# aqc-dac-io-board.net
KiCad netlist of a schematic drawn in EAGLE
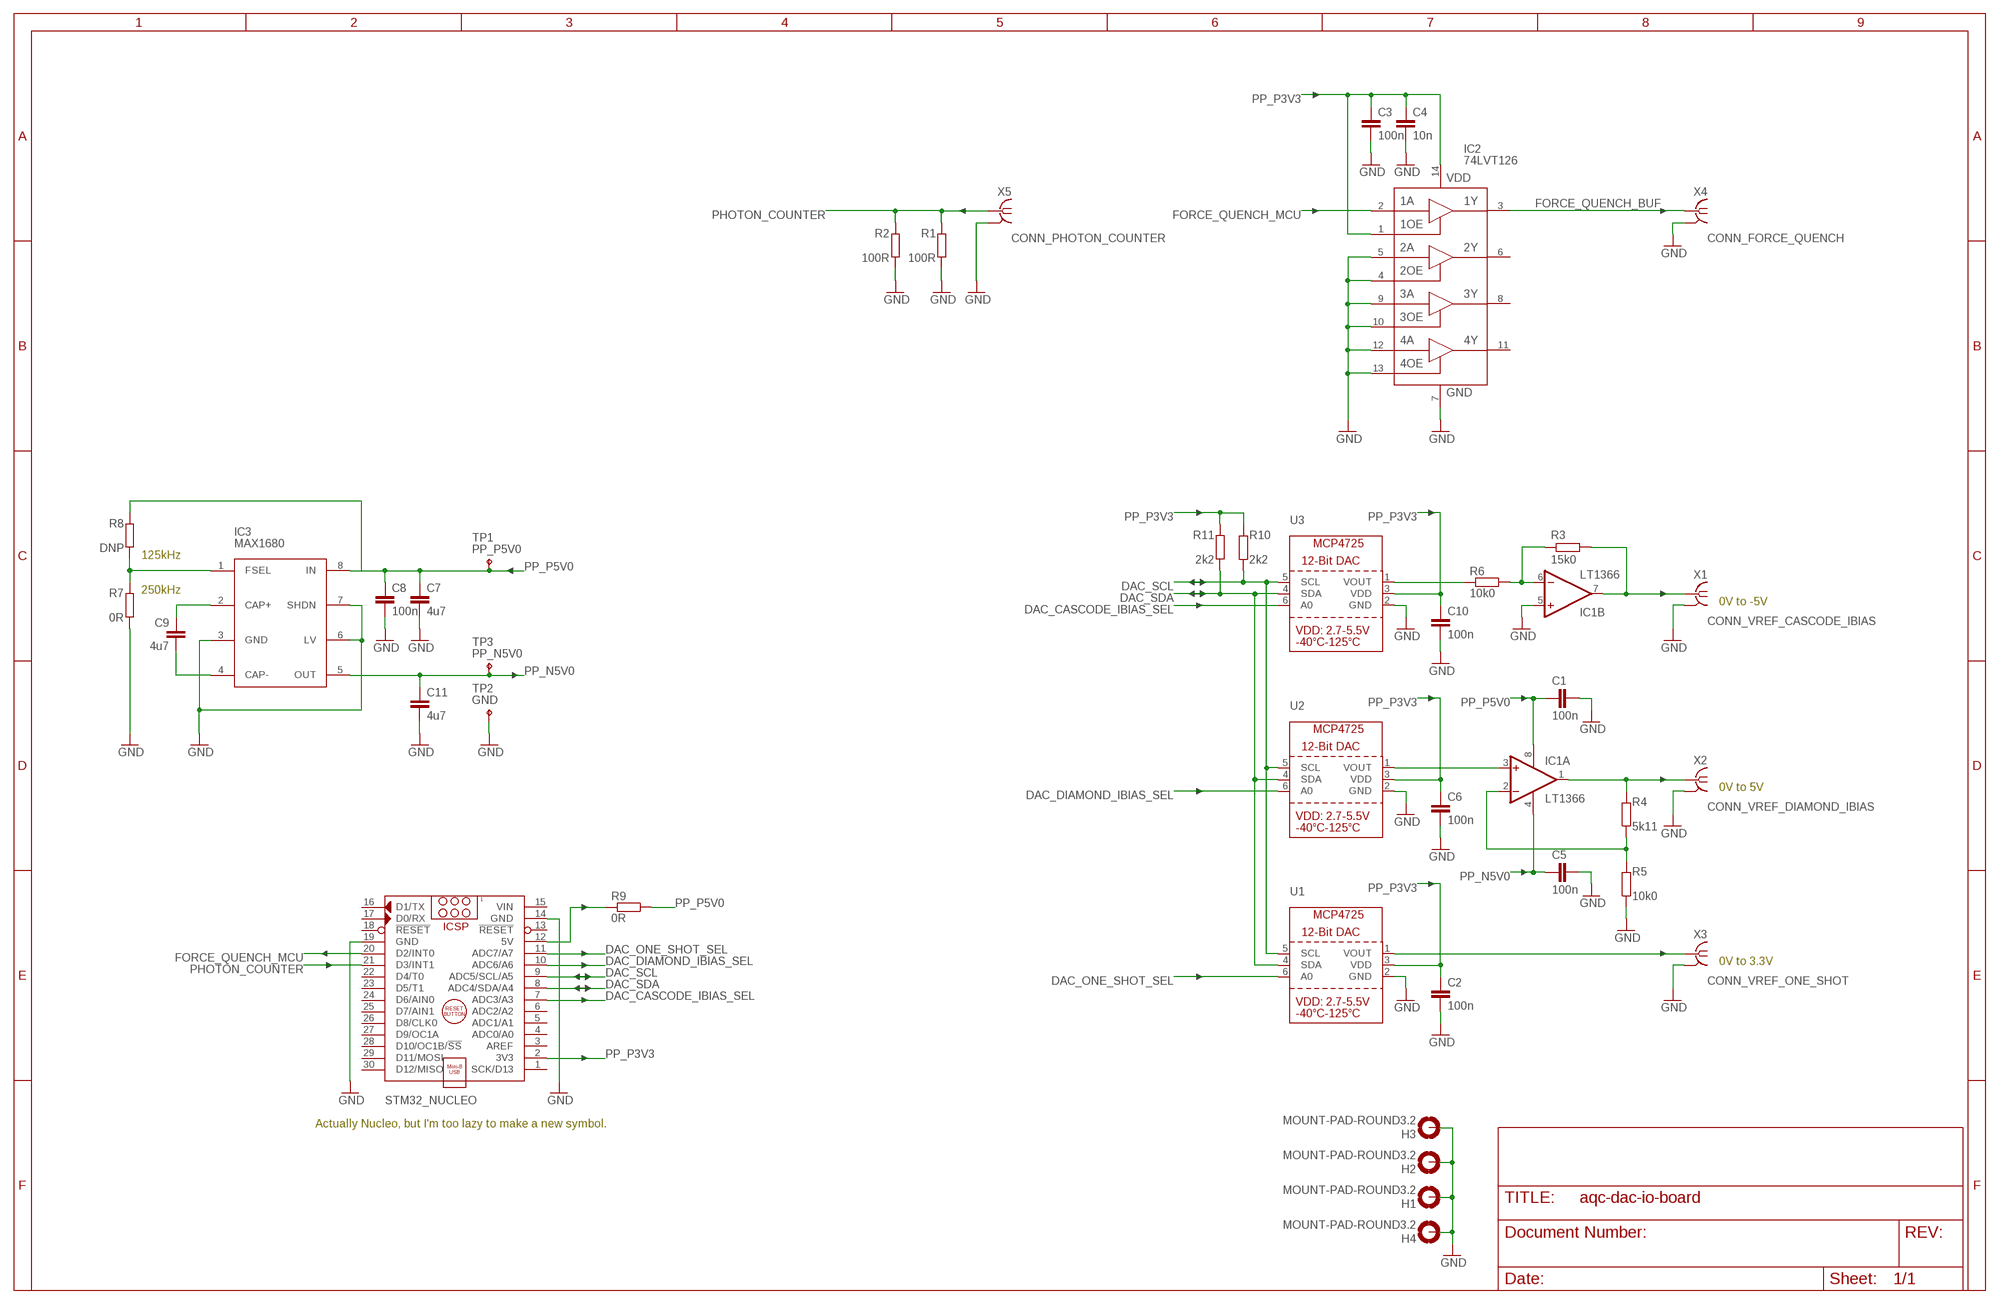
[diagram p0: schematic, sheet 1]

(export (version "E")
  (design (tool "Eeschema 10.0.6"))
  (components
    (comp (ref "C1")
      (value "100n")
      (footprint "eagle-import:C0603")
      (libsource (lib "eagle-import") (part "C-EUC0603"))
    )
    (comp (ref "C2")
      (value "100n")
      (footprint "eagle-import:C0603")
      (libsource (lib "eagle-import") (part "C-EUC0603"))
    )
    (comp (ref "C3")
      (value "100n")
      (footprint "eagle-import:C0603")
      (libsource (lib "eagle-import") (part "C-EUC0603"))
    )
    (comp (ref "C4")
      (value "10n")
      (footprint "eagle-import:C0603")
      (libsource (lib "eagle-import") (part "C-EUC0603"))
    )
    (comp (ref "C5")
      (value "100n")
      (footprint "eagle-import:C0603")
      (libsource (lib "eagle-import") (part "C-EUC0603"))
    )
    (comp (ref "C6")
      (value "100n")
      (footprint "eagle-import:C0603")
      (libsource (lib "eagle-import") (part "C-EUC0603"))
    )
    (comp (ref "C7")
      (value "4u7")
      (footprint "eagle-import:C0805")
      (libsource (lib "eagle-import") (part "C-EUC0805"))
    )
    (comp (ref "C8")
      (value "100n")
      (footprint "eagle-import:C0603")
      (libsource (lib "eagle-import") (part "C-EUC0603"))
    )
    (comp (ref "C9")
      (value "4u7")
      (footprint "eagle-import:C0805")
      (libsource (lib "eagle-import") (part "C-EUC0805"))
    )
    (comp (ref "C10")
      (value "100n")
      (footprint "eagle-import:C0603")
      (libsource (lib "eagle-import") (part "C-EUC0603"))
    )
    (comp (ref "C11")
      (value "4u7")
      (footprint "eagle-import:C0805")
      (libsource (lib "eagle-import") (part "C-EUC0805"))
    )
    (comp (ref "H1")
      (value "MOUNT-PAD-ROUND3.2")
      (footprint "eagle-import:3,2-PAD")
      (libsource (lib "eagle-import") (part "MOUNT-PAD-ROUND3.2"))
    )
    (comp (ref "H2")
      (value "MOUNT-PAD-ROUND3.2")
      (footprint "eagle-import:3,2-PAD")
      (libsource (lib "eagle-import") (part "MOUNT-PAD-ROUND3.2"))
    )
    (comp (ref "H3")
      (value "MOUNT-PAD-ROUND3.2")
      (footprint "eagle-import:3,2-PAD")
      (libsource (lib "eagle-import") (part "MOUNT-PAD-ROUND3.2"))
    )
    (comp (ref "H4")
      (value "MOUNT-PAD-ROUND3.2")
      (footprint "eagle-import:3,2-PAD")
      (libsource (lib "eagle-import") (part "MOUNT-PAD-ROUND3.2"))
    )
    (comp (ref "IC1")
      (value "LT1366")
      (footprint "eagle-import:SO08")
      (libsource (lib "eagle-import") (part "LT1366"))
    )
    (comp (ref "IC2")
      (value "74LVT126")
      (footprint "eagle-import:SO14")
      (libsource (lib "eagle-import") (part "74LVT126"))
    )
    (comp (ref "IC3")
      (value "MAX1680")
      (footprint "eagle-import:SO8")
      (libsource (lib "eagle-import") (part "MAX1680/1"))
    )
    (comp (ref "R1")
      (value "100R")
      (footprint "eagle-import:R0603")
      (libsource (lib "eagle-import") (part "R-EU_R0603"))
    )
    (comp (ref "R2")
      (value "100R")
      (footprint "eagle-import:R0603")
      (libsource (lib "eagle-import") (part "R-EU_R0603"))
    )
    (comp (ref "R3")
      (value "15k0")
      (footprint "eagle-import:R0603")
      (libsource (lib "eagle-import") (part "R-EU_R0603"))
    )
    (comp (ref "R4")
      (value "5k11")
      (footprint "eagle-import:R0603")
      (libsource (lib "eagle-import") (part "R-EU_R0603"))
    )
    (comp (ref "R5")
      (value "10k0")
      (footprint "eagle-import:R0603")
      (libsource (lib "eagle-import") (part "R-EU_R0603"))
    )
    (comp (ref "R6")
      (value "10k0")
      (footprint "eagle-import:R0603")
      (libsource (lib "eagle-import") (part "R-EU_R0603"))
    )
    (comp (ref "R7")
      (value "0R")
      (footprint "eagle-import:R0603")
      (libsource (lib "eagle-import") (part "R-EU_R0603"))
    )
    (comp (ref "R8")
      (value "DNP")
      (footprint "eagle-import:R0603")
      (libsource (lib "eagle-import") (part "R-EU_R0603"))
    )
    (comp (ref "R9")
      (value "0R")
      (footprint "eagle-import:R0603")
      (libsource (lib "eagle-import") (part "R-EU_R0603"))
    )
    (comp (ref "R10")
      (value "2k2")
      (footprint "eagle-import:R0603")
      (libsource (lib "eagle-import") (part "R-EU_R0603"))
    )
    (comp (ref "R11")
      (value "2k2")
      (footprint "eagle-import:R0603")
      (libsource (lib "eagle-import") (part "R-EU_R0603"))
    )
    (comp (ref "STM32_NUCLEO")
      (value "ARDUINO_NANO")
      (footprint "eagle-import:ARDUINO_NANO")
      (libsource (lib "eagle-import") (part "ARDUINO_NANO"))
    )
    (comp (ref "TP1")
      (value "PP_P5V0")
      (footprint "eagle-import:KEYSTONE_5000_MINIATURE")
      (libsource (lib "eagle-import") (part "KEYSTONE_5000"))
    )
    (comp (ref "TP2")
      (value "GND")
      (footprint "eagle-import:KEYSTONE_5000_MINIATURE")
      (libsource (lib "eagle-import") (part "KEYSTONE_5000"))
    )
    (comp (ref "TP3")
      (value "PP_N5V0")
      (footprint "eagle-import:KEYSTONE_5000_MINIATURE")
      (libsource (lib "eagle-import") (part "KEYSTONE_5000"))
    )
    (comp (ref "U1")
      (value "DAC_MCP4725")
      (footprint "eagle-import:SOT23-6")
      (libsource (lib "eagle-import") (part "DAC_MCP4725"))
    )
    (comp (ref "U2")
      (value "DAC_MCP4725")
      (footprint "eagle-import:SOT23-6")
      (libsource (lib "eagle-import") (part "DAC_MCP4725"))
    )
    (comp (ref "U3")
      (value "DAC_MCP4725")
      (footprint "eagle-import:SOT23-6")
      (libsource (lib "eagle-import") (part "DAC_MCP4725"))
    )
    (comp (ref "X1")
      (value "CONN_VREF_CASCODE_IBIAS")
      (footprint "eagle-import:J502-ND-142-0701-801_806")
      (fields (field (name "MF") "JOHNSON COMPONENTS") (field (name "MPN") "142-0701-801"))
      (libsource (lib "eagle-import") (part "SMA-142-0701-801/806"))
    )
    (comp (ref "X2")
      (value "CONN_VREF_DIAMOND_IBIAS")
      (footprint "eagle-import:J502-ND-142-0701-801_806")
      (fields (field (name "MF") "JOHNSON COMPONENTS") (field (name "MPN") "142-0701-801"))
      (libsource (lib "eagle-import") (part "SMA-142-0701-801/806"))
    )
    (comp (ref "X3")
      (value "CONN_VREF_ONE_SHOT")
      (footprint "eagle-import:J502-ND-142-0701-801_806")
      (fields (field (name "MF") "JOHNSON COMPONENTS") (field (name "MPN") "142-0701-801"))
      (libsource (lib "eagle-import") (part "SMA-142-0701-801/806"))
    )
    (comp (ref "X4")
      (value "CONN_FORCE_QUENCH")
      (footprint "eagle-import:J502-ND-142-0701-801_806")
      (fields (field (name "MF") "JOHNSON COMPONENTS") (field (name "MPN") "142-0701-801"))
      (libsource (lib "eagle-import") (part "SMA-142-0701-801/806"))
    )
    (comp (ref "X5")
      (value "CONN_PHOTON_COUNTER")
      (footprint "eagle-import:J502-ND-142-0701-801_806")
      (fields (field (name "MF") "JOHNSON COMPONENTS") (field (name "MPN") "142-0701-801"))
      (libsource (lib "eagle-import") (part "SMA-142-0701-801/806"))
    )
  )
  (nets
    (net (code "1") (name "/DAC_CASCODE_IBIAS_SEL") (class "Default")
      (node (ref "STM32_NUCLEO") (pin "7") (pinfunction "ADC3/A3_7") (pintype "bidirectional"))
      (node (ref "U3") (pin "6") (pinfunction "A0_6") (pintype "input"))
    )
    (net (code "2") (name "/DAC_DIAMOND_IBIAS_SEL") (class "Default")
      (node (ref "STM32_NUCLEO") (pin "10") (pinfunction "ADC6/A6_10") (pintype "bidirectional"))
      (node (ref "U2") (pin "6") (pinfunction "A0_6") (pintype "input"))
    )
    (net (code "3") (name "/DAC_ONE_SHOT_SEL") (class "Default")
      (node (ref "STM32_NUCLEO") (pin "11") (pinfunction "ADC7/A7_11") (pintype "bidirectional"))
      (node (ref "U1") (pin "6") (pinfunction "A0_6") (pintype "input"))
    )
    (net (code "4") (name "/DAC_SCL") (class "Default")
      (node (ref "R10") (pin "1") (pinfunction "1_1") (pintype "passive"))
      (node (ref "STM32_NUCLEO") (pin "9") (pinfunction "ADC5/SCL/A5_9") (pintype "bidirectional"))
      (node (ref "U1") (pin "5") (pinfunction "SCL_5") (pintype "bidirectional"))
      (node (ref "U2") (pin "5") (pinfunction "SCL_5") (pintype "bidirectional"))
      (node (ref "U3") (pin "5") (pinfunction "SCL_5") (pintype "bidirectional"))
    )
    (net (code "5") (name "/DAC_SDA") (class "Default")
      (node (ref "R11") (pin "1") (pinfunction "1_1") (pintype "passive"))
      (node (ref "STM32_NUCLEO") (pin "8") (pinfunction "ADC4/SDA/A4_8") (pintype "bidirectional"))
      (node (ref "U1") (pin "4") (pinfunction "SDA_4") (pintype "bidirectional"))
      (node (ref "U2") (pin "4") (pinfunction "SDA_4") (pintype "bidirectional"))
      (node (ref "U3") (pin "4") (pinfunction "SDA_4") (pintype "bidirectional"))
    )
    (net (code "6") (name "/FORCE_QUENCH_BUF") (class "Default")
      (node (ref "IC2") (pin "3") (pinfunction "1Y_3") (pintype "bidirectional"))
      (node (ref "X4") (pin "1") (pinfunction "1_1") (pintype "passive"))
    )
    (net (code "7") (name "/FORCE_QUENCH_MCU") (class "Default")
      (node (ref "IC2") (pin "2") (pinfunction "1A_2") (pintype "bidirectional"))
      (node (ref "STM32_NUCLEO") (pin "20") (pinfunction "D2/INT0_20") (pintype "bidirectional"))
    )
    (net (code "8") (name "/PHOTON_COUNTER") (class "Default")
      (node (ref "R1") (pin "2") (pinfunction "2_2") (pintype "passive"))
      (node (ref "R2") (pin "2") (pinfunction "2_2") (pintype "passive"))
      (node (ref "STM32_NUCLEO") (pin "21") (pinfunction "D3/INT1_21") (pintype "bidirectional"))
      (node (ref "X5") (pin "1") (pinfunction "1_1") (pintype "passive"))
    )
    (net (code "9") (name "/PP_N5V0") (class "Default")
      (node (ref "C11") (pin "1") (pinfunction "1_1") (pintype "passive"))
      (node (ref "C5") (pin "1") (pinfunction "1_1") (pintype "passive"))
      (node (ref "IC1") (pin "4") (pinfunction "V-_4") (pintype "power_in"))
      (node (ref "IC3") (pin "5") (pinfunction "OUT_5") (pintype "bidirectional"))
      (node (ref "TP3") (pin "P$1") (pinfunction "P$1_P$1") (pintype "bidirectional"))
    )
    (net (code "10") (name "/PP_P3V3") (class "Default")
      (node (ref "C10") (pin "1") (pinfunction "1_1") (pintype "passive"))
      (node (ref "C2") (pin "1") (pinfunction "1_1") (pintype "passive"))
      (node (ref "C3") (pin "1") (pinfunction "1_1") (pintype "passive"))
      (node (ref "C4") (pin "1") (pinfunction "1_1") (pintype "passive"))
      (node (ref "C6") (pin "1") (pinfunction "1_1") (pintype "passive"))
      (node (ref "IC2") (pin "1") (pinfunction "1OE_1") (pintype "bidirectional"))
      (node (ref "IC2") (pin "14") (pinfunction "VDD_14") (pintype "bidirectional"))
      (node (ref "R10") (pin "2") (pinfunction "2_2") (pintype "passive"))
      (node (ref "R11") (pin "2") (pinfunction "2_2") (pintype "passive"))
      (node (ref "STM32_NUCLEO") (pin "2") (pinfunction "3V3_2") (pintype "output"))
      (node (ref "U1") (pin "3") (pinfunction "VDD_3") (pintype "power_in"))
      (node (ref "U2") (pin "3") (pinfunction "VDD_3") (pintype "power_in"))
      (node (ref "U3") (pin "3") (pinfunction "VDD_3") (pintype "power_in"))
    )
    (net (code "11") (name "/PP_P5V0") (class "Default")
      (node (ref "C1") (pin "1") (pinfunction "1_1") (pintype "passive"))
      (node (ref "C7") (pin "1") (pinfunction "1_1") (pintype "passive"))
      (node (ref "C8") (pin "1") (pinfunction "1_1") (pintype "passive"))
      (node (ref "IC1") (pin "8") (pinfunction "V+_8") (pintype "power_in"))
      (node (ref "IC3") (pin "8") (pinfunction "IN_8") (pintype "bidirectional"))
      (node (ref "R8") (pin "2") (pinfunction "2_2") (pintype "passive"))
      (node (ref "R9") (pin "1") (pinfunction "1_1") (pintype "passive"))
      (node (ref "TP1") (pin "P$1") (pinfunction "P$1_P$1") (pintype "bidirectional"))
    )
    (net (code "12") (name "/VIN") (class "Default")
      (node (ref "STM32_NUCLEO") (pin "15") (pinfunction "VIN_15") (pintype "power_in"))
    )
    (net (code "13") (name "GND") (class "Default")
      (node (ref "C1") (pin "2") (pinfunction "2_2") (pintype "passive"))
      (node (ref "C10") (pin "2") (pinfunction "2_2") (pintype "passive"))
      (node (ref "C11") (pin "2") (pinfunction "2_2") (pintype "passive"))
      (node (ref "C2") (pin "2") (pinfunction "2_2") (pintype "passive"))
      (node (ref "C3") (pin "2") (pinfunction "2_2") (pintype "passive"))
      (node (ref "C4") (pin "2") (pinfunction "2_2") (pintype "passive"))
      (node (ref "C5") (pin "2") (pinfunction "2_2") (pintype "passive"))
      (node (ref "C6") (pin "2") (pinfunction "2_2") (pintype "passive"))
      (node (ref "C7") (pin "2") (pinfunction "2_2") (pintype "passive"))
      (node (ref "C8") (pin "2") (pinfunction "2_2") (pintype "passive"))
      (node (ref "H1") (pin "B3,2") (pinfunction "MOUNT_B3,2") (pintype "passive"))
      (node (ref "H2") (pin "B3,2") (pinfunction "MOUNT_B3,2") (pintype "passive"))
      (node (ref "H3") (pin "B3,2") (pinfunction "MOUNT_B3,2") (pintype "passive"))
      (node (ref "H4") (pin "B3,2") (pinfunction "MOUNT_B3,2") (pintype "passive"))
      (node (ref "IC1") (pin "5") (pinfunction "+IN_5") (pintype "input"))
      (node (ref "IC2") (pin "10") (pinfunction "3OE_10") (pintype "bidirectional"))
      (node (ref "IC2") (pin "12") (pinfunction "4A_12") (pintype "bidirectional"))
      (node (ref "IC2") (pin "13") (pinfunction "4OE_13") (pintype "bidirectional"))
      (node (ref "IC2") (pin "4") (pinfunction "2OE_4") (pintype "bidirectional"))
      (node (ref "IC2") (pin "5") (pinfunction "2A_5") (pintype "bidirectional"))
      (node (ref "IC2") (pin "7") (pinfunction "GND_7") (pintype "bidirectional"))
      (node (ref "IC2") (pin "9") (pinfunction "3A_9") (pintype "bidirectional"))
      (node (ref "IC3") (pin "3") (pinfunction "GND_3") (pintype "bidirectional"))
      (node (ref "IC3") (pin "6") (pinfunction "LV_6") (pintype "bidirectional"))
      (node (ref "IC3") (pin "7") (pinfunction "SHDN_7") (pintype "bidirectional"))
      (node (ref "R1") (pin "1") (pinfunction "1_1") (pintype "passive"))
      (node (ref "R2") (pin "1") (pinfunction "1_1") (pintype "passive"))
      (node (ref "R5") (pin "1") (pinfunction "1_1") (pintype "passive"))
      (node (ref "R7") (pin "1") (pinfunction "1_1") (pintype "passive"))
      (node (ref "STM32_NUCLEO") (pin "14") (pinfunction "GND_14") (pintype "power_in"))
      (node (ref "STM32_NUCLEO") (pin "19") (pinfunction "GND_19") (pintype "power_in"))
      (node (ref "TP2") (pin "P$1") (pinfunction "P$1_P$1") (pintype "bidirectional"))
      (node (ref "U1") (pin "2") (pinfunction "GND_2") (pintype "power_in"))
      (node (ref "U2") (pin "2") (pinfunction "GND_2") (pintype "power_in"))
      (node (ref "U3") (pin "2") (pinfunction "GND_2") (pintype "power_in"))
      (node (ref "X1") (pin "G@1") (pinfunction "GND_G@1") (pintype "power_in"))
      (node (ref "X2") (pin "G@1") (pinfunction "GND_G@1") (pintype "power_in"))
      (node (ref "X3") (pin "G@1") (pinfunction "GND_G@1") (pintype "power_in"))
      (node (ref "X4") (pin "G@1") (pinfunction "GND_G@1") (pintype "power_in"))
      (node (ref "X5") (pin "G@1") (pinfunction "GND_G@1") (pintype "power_in"))
    )
    (net (code "14") (name "Net-(IC1A-+IN)") (class "Default")
      (node (ref "IC1") (pin "3") (pinfunction "+IN_3") (pintype "input"))
      (node (ref "U2") (pin "1") (pinfunction "VOUT_1") (pintype "output"))
    )
    (net (code "15") (name "Net-(IC1A--IN)") (class "Default")
      (node (ref "IC1") (pin "2") (pinfunction "-IN_2") (pintype "input"))
      (node (ref "R4") (pin "1") (pinfunction "1_1") (pintype "passive"))
      (node (ref "R5") (pin "2") (pinfunction "2_2") (pintype "passive"))
    )
    (net (code "16") (name "Net-(IC1A-OUT)") (class "Default")
      (node (ref "IC1") (pin "1") (pinfunction "OUT_1") (pintype "output"))
      (node (ref "R4") (pin "2") (pinfunction "2_2") (pintype "passive"))
      (node (ref "X2") (pin "1") (pinfunction "1_1") (pintype "passive"))
    )
    (net (code "17") (name "Net-(IC1B--IN)") (class "Default")
      (node (ref "IC1") (pin "6") (pinfunction "-IN_6") (pintype "input"))
      (node (ref "R3") (pin "2") (pinfunction "2_2") (pintype "passive"))
      (node (ref "R6") (pin "1") (pinfunction "1_1") (pintype "passive"))
    )
    (net (code "18") (name "Net-(IC1B-OUT)") (class "Default")
      (node (ref "IC1") (pin "7") (pinfunction "OUT_7") (pintype "output"))
      (node (ref "R3") (pin "1") (pinfunction "1_1") (pintype "passive"))
      (node (ref "X1") (pin "1") (pinfunction "1_1") (pintype "passive"))
    )
    (net (code "19") (name "Net-(IC3-CAP+)") (class "Default")
      (node (ref "C9") (pin "1") (pinfunction "1_1") (pintype "passive"))
      (node (ref "IC3") (pin "2") (pinfunction "CAP+_2") (pintype "bidirectional"))
    )
    (net (code "20") (name "Net-(IC3-CAP-)") (class "Default")
      (node (ref "C9") (pin "2") (pinfunction "2_2") (pintype "passive"))
      (node (ref "IC3") (pin "4") (pinfunction "CAP-_4") (pintype "bidirectional"))
    )
    (net (code "21") (name "Net-(IC3-FSEL)") (class "Default")
      (node (ref "IC3") (pin "1") (pinfunction "FSEL_1") (pintype "bidirectional"))
      (node (ref "R7") (pin "2") (pinfunction "2_2") (pintype "passive"))
      (node (ref "R8") (pin "1") (pinfunction "1_1") (pintype "passive"))
    )
    (net (code "22") (name "Net-(STM32_NUCLEO-5V)") (class "Default")
      (node (ref "R9") (pin "2") (pinfunction "2_2") (pintype "passive"))
      (node (ref "STM32_NUCLEO") (pin "12") (pinfunction "5V_12") (pintype "power_in"))
    )
    (net (code "23") (name "Net-(U1-VOUT)") (class "Default")
      (node (ref "U1") (pin "1") (pinfunction "VOUT_1") (pintype "output"))
      (node (ref "X3") (pin "1") (pinfunction "1_1") (pintype "passive"))
    )
    (net (code "24") (name "Net-(U3-VOUT)") (class "Default")
      (node (ref "R6") (pin "2") (pinfunction "2_2") (pintype "passive"))
      (node (ref "U3") (pin "1") (pinfunction "VOUT_1") (pintype "output"))
    )
    (net (code "25") (name "unconnected-(IC2-2Y-Pad6)") (class "Default")
      (node (ref "IC2") (pin "6") (pinfunction "2Y_6") (pintype "bidirectional"))
    )
    (net (code "26") (name "unconnected-(IC2-3Y-Pad8)") (class "Default")
      (node (ref "IC2") (pin "8") (pinfunction "3Y_8") (pintype "bidirectional"))
    )
    (net (code "27") (name "unconnected-(IC2-4Y-Pad11)") (class "Default")
      (node (ref "IC2") (pin "11") (pinfunction "4Y_11") (pintype "bidirectional"))
    )
    (net (code "28") (name "unconnected-(STM32_NUCLEO-ADC0{slash}A0-Pad4)") (class "Default")
      (node (ref "STM32_NUCLEO") (pin "4") (pinfunction "ADC0/A0_4") (pintype "bidirectional"))
    )
    (net (code "29") (name "unconnected-(STM32_NUCLEO-ADC1{slash}A1-Pad5)") (class "Default")
      (node (ref "STM32_NUCLEO") (pin "5") (pinfunction "ADC1/A1_5") (pintype "bidirectional"))
    )
    (net (code "30") (name "unconnected-(STM32_NUCLEO-ADC2{slash}A2-Pad6)") (class "Default")
      (node (ref "STM32_NUCLEO") (pin "6") (pinfunction "ADC2/A2_6") (pintype "bidirectional"))
    )
    (net (code "31") (name "unconnected-(STM32_NUCLEO-AREF-Pad3)") (class "Default")
      (node (ref "STM32_NUCLEO") (pin "3") (pinfunction "AREF_3") (pintype "input"))
    )
    (net (code "32") (name "unconnected-(STM32_NUCLEO-D0{slash}RX-Pad17)") (class "Default")
      (node (ref "STM32_NUCLEO") (pin "17") (pinfunction "D0/RX_17") (pintype "bidirectional"))
    )
    (net (code "33") (name "unconnected-(STM32_NUCLEO-D1{slash}TX-Pad16)") (class "Default")
      (node (ref "STM32_NUCLEO") (pin "16") (pinfunction "D1/TX_16") (pintype "bidirectional"))
    )
    (net (code "34") (name "unconnected-(STM32_NUCLEO-D4{slash}T0-Pad22)") (class "Default")
      (node (ref "STM32_NUCLEO") (pin "22") (pinfunction "D4/T0_22") (pintype "bidirectional"))
    )
    (net (code "35") (name "unconnected-(STM32_NUCLEO-D5{slash}T1-Pad23)") (class "Default")
      (node (ref "STM32_NUCLEO") (pin "23") (pinfunction "D5/T1_23") (pintype "bidirectional"))
    )
    (net (code "36") (name "unconnected-(STM32_NUCLEO-D6{slash}AIN0-Pad24)") (class "Default")
      (node (ref "STM32_NUCLEO") (pin "24") (pinfunction "D6/AIN0_24") (pintype "bidirectional"))
    )
    (net (code "37") (name "unconnected-(STM32_NUCLEO-D7{slash}AIN1-Pad25)") (class "Default")
      (node (ref "STM32_NUCLEO") (pin "25") (pinfunction "D7/AIN1_25") (pintype "bidirectional"))
    )
    (net (code "38") (name "unconnected-(STM32_NUCLEO-D8{slash}CLK0-Pad26)") (class "Default")
      (node (ref "STM32_NUCLEO") (pin "26") (pinfunction "D8/CLK0_26") (pintype "bidirectional"))
    )
    (net (code "39") (name "unconnected-(STM32_NUCLEO-D9{slash}OC1A-Pad27)") (class "Default")
      (node (ref "STM32_NUCLEO") (pin "27") (pinfunction "D9/OC1A_27") (pintype "bidirectional"))
    )
    (net (code "40") (name "unconnected-(STM32_NUCLEO-D10{slash}OC1B{slash}~{SS}-Pad28)") (class "Default")
      (node (ref "STM32_NUCLEO") (pin "28") (pinfunction "D10/OC1B/~{SS}_28") (pintype "bidirectional"))
    )
    (net (code "41") (name "unconnected-(STM32_NUCLEO-D11{slash}MOSI-Pad29)") (class "Default")
      (node (ref "STM32_NUCLEO") (pin "29") (pinfunction "D11/MOSI_29") (pintype "bidirectional"))
    )
    (net (code "42") (name "unconnected-(STM32_NUCLEO-D12{slash}MISO-Pad30)") (class "Default")
      (node (ref "STM32_NUCLEO") (pin "30") (pinfunction "D12/MISO_30") (pintype "bidirectional"))
    )
    (net (code "43") (name "unconnected-(STM32_NUCLEO-SCK{slash}D13-Pad1)") (class "Default")
      (node (ref "STM32_NUCLEO") (pin "1") (pinfunction "SCK/D13_1") (pintype "bidirectional"))
    )
    (net (code "44") (name "unconnected-(STM32_NUCLEO-~{RESET}-Pad13)") (class "Default")
      (node (ref "STM32_NUCLEO") (pin "13") (pinfunction "~{RESET}_13") (pintype "input"))
    )
    (net (code "45") (name "unconnected-(STM32_NUCLEO-~{RESET}-Pad18)") (class "Default")
      (node (ref "STM32_NUCLEO") (pin "18") (pinfunction "~{RESET}_18") (pintype "input"))
    )
  )
)
